# SwitchV1.net
KiCad netlist of a schematic drawn in EAGLE
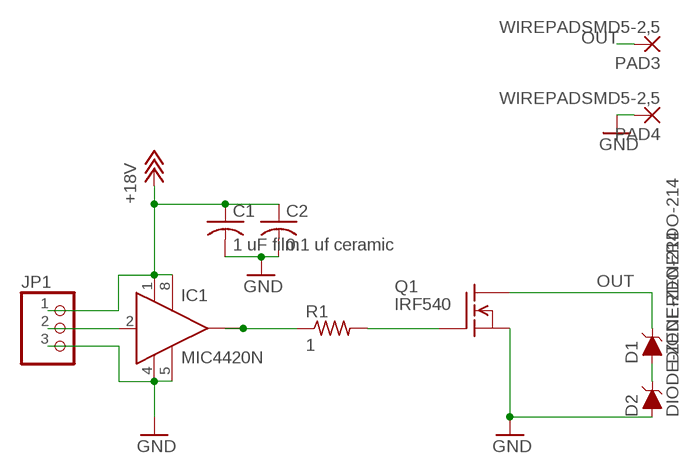
[diagram p0: schematic, sheet 1]

(export (version "E")
  (design (tool "Eeschema 10.0.6"))
  (components
    (comp (ref "C1")
      (value "1 uF film")
      (footprint "eagle-import:C050-045X075")
      (libsource (lib "eagle-import") (part "C-US050-045X075"))
    )
    (comp (ref "C2")
      (value "0.1 uf ceramic")
      (footprint "eagle-import:C025-030X050")
      (libsource (lib "eagle-import") (part "C-US025-030X050"))
    )
    (comp (ref "D1")
      (value "DIODE-ZENERDO-214")
      (footprint "eagle-import:SMA-DIODE")
      (libsource (lib "eagle-import") (part "DIODE-ZENERDO-214"))
    )
    (comp (ref "D2")
      (value "DIODE-ZENERDO-214")
      (footprint "eagle-import:SMA-DIODE")
      (libsource (lib "eagle-import") (part "DIODE-ZENERDO-214"))
    )
    (comp (ref "IC1")
      (value "MIC4420N")
      (footprint "eagle-import:DIL08")
      (libsource (lib "eagle-import") (part "MIC4420N"))
    )
    (comp (ref "JP1")
      (value "PINHD-1X3")
      (footprint "eagle-import:1X03")
      (libsource (lib "eagle-import") (part "PINHD-1X3"))
    )
    (comp (ref "PAD3")
      (value "WIREPADSMD5-2,5")
      (footprint "eagle-import:5-2,5")
      (libsource (lib "eagle-import") (part "WIREPADSMD5-2,5"))
    )
    (comp (ref "PAD4")
      (value "WIREPADSMD5-2,5")
      (footprint "eagle-import:5-2,5")
      (libsource (lib "eagle-import") (part "WIREPADSMD5-2,5"))
    )
    (comp (ref "Q1")
      (value "IRF540")
      (footprint "eagle-import:TO220")
      (libsource (lib "eagle-import") (part "IRF540"))
    )
    (comp (ref "R1")
      (value "1")
      (footprint "eagle-import:0207_7")
      (libsource (lib "eagle-import") (part "R-US_0207/7"))
    )
  )
  (nets
    (net (code "1") (name "+18V") (class "Default")
      (node (ref "C1") (pin "1") (pinfunction "1_1") (pintype "passive"))
      (node (ref "C2") (pin "1") (pinfunction "1_1") (pintype "passive"))
      (node (ref "IC1") (pin "1") (pinfunction "VS_1") (pintype "power_in"))
      (node (ref "IC1") (pin "8") (pinfunction "VS1_8") (pintype "power_in"))
      (node (ref "JP1") (pin "1") (pinfunction "1_1") (pintype "passive"))
    )
    (net (code "2") (name "/OUT") (class "Default")
      (node (ref "D1") (pin "C") (pinfunction "C_C") (pintype "passive"))
      (node (ref "PAD3") (pin "1") (pinfunction "P_1") (pintype "passive"))
      (node (ref "Q1") (pin "2") (pinfunction "D_2") (pintype "passive"))
    )
    (net (code "3") (name "GND") (class "Default")
      (node (ref "C1") (pin "2") (pinfunction "2_2") (pintype "passive"))
      (node (ref "C2") (pin "2") (pinfunction "2_2") (pintype "passive"))
      (node (ref "D2") (pin "A") (pinfunction "A_A") (pintype "passive"))
      (node (ref "IC1") (pin "4") (pinfunction "GND_4") (pintype "power_in"))
      (node (ref "IC1") (pin "5") (pinfunction "GND1_5") (pintype "power_in"))
      (node (ref "JP1") (pin "3") (pinfunction "3_3") (pintype "passive"))
      (node (ref "PAD4") (pin "1") (pinfunction "P_1") (pintype "passive"))
      (node (ref "Q1") (pin "3") (pinfunction "S_3") (pintype "passive"))
    )
    (net (code "4") (name "Net-(D1-PadA)") (class "Default")
      (node (ref "D1") (pin "A") (pinfunction "A_A") (pintype "passive"))
      (node (ref "D2") (pin "C") (pinfunction "C_C") (pintype "passive"))
    )
    (net (code "5") (name "Net-(IC1-IN)") (class "Default")
      (node (ref "IC1") (pin "2") (pinfunction "IN_2") (pintype "input"))
      (node (ref "JP1") (pin "2") (pinfunction "2_2") (pintype "passive"))
    )
    (net (code "6") (name "Net-(IC1-OUT-Pad6)") (class "Default")
      (node (ref "IC1") (pin "6") (pinfunction "OUT_6") (pintype "passive"))
      (node (ref "IC1") (pin "7") (pinfunction "OUT_7") (pintype "passive"))
      (node (ref "R1") (pin "1") (pinfunction "1_1") (pintype "passive"))
    )
    (net (code "7") (name "Net-(Q1-G)") (class "Default")
      (node (ref "Q1") (pin "1") (pinfunction "G_1") (pintype "passive"))
      (node (ref "R1") (pin "2") (pinfunction "2_2") (pintype "passive"))
    )
  )
)
